# WindVane_1.net
KiCad netlist of a schematic drawn in EAGLE
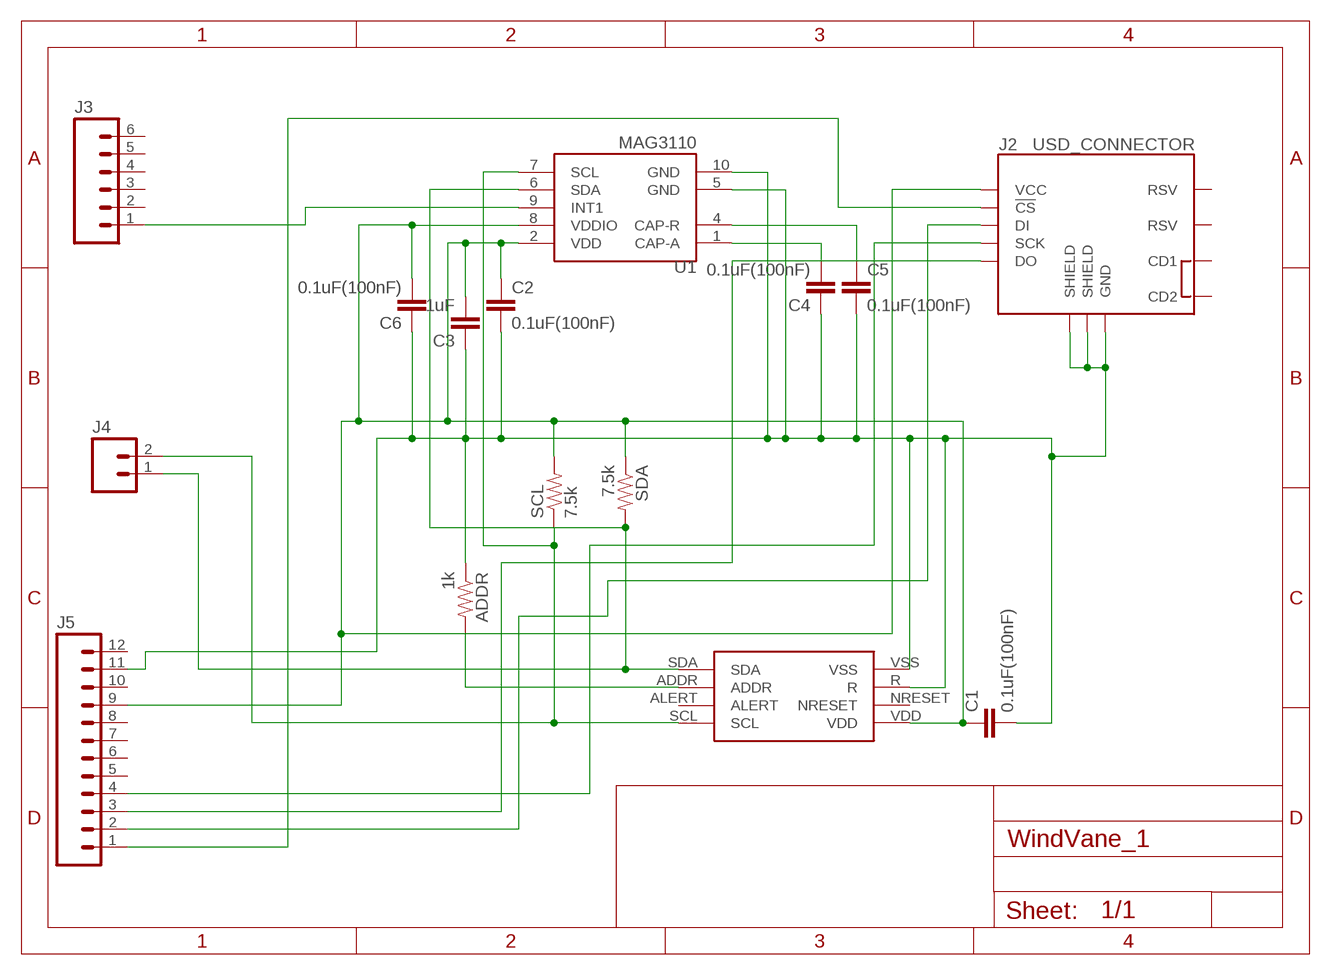
[diagram p0: schematic, sheet 1]

(export (version "E")
  (design (tool "Eeschema 10.0.6"))
  (components
    (comp (ref "ADDR")
      (value "1k")
      (footprint "eagle-import:1206")
      (libsource (lib "eagle-import") (part "RESISTOR1206"))
    )
    (comp (ref "C1")
      (value "0.1uF(100nF)")
      (footprint "eagle-import:0603-CAP")
      (libsource (lib "eagle-import") (part "SparkFun-Passives_CAP0603-CAP"))
    )
    (comp (ref "C2")
      (value "0.1uF(100nF)")
      (footprint "eagle-import:0603-CAP")
      (libsource (lib "eagle-import") (part "0.1UF-25V(+80/-20%)(0603)"))
    )
    (comp (ref "C3")
      (value "1uF")
      (footprint "eagle-import:0402-CAP")
      (libsource (lib "eagle-import") (part "CAP0402-CAP"))
    )
    (comp (ref "C4")
      (value "0.1uF(100nF)")
      (footprint "eagle-import:0603-CAP")
      (libsource (lib "eagle-import") (part "0.1UF-25V(+80/-20%)(0603)"))
    )
    (comp (ref "C5")
      (value "0.1uF(100nF)")
      (footprint "eagle-import:0603-CAP")
      (libsource (lib "eagle-import") (part "0.1UF-25V(+80/-20%)(0603)"))
    )
    (comp (ref "C6")
      (value "0.1uF(100nF)")
      (footprint "eagle-import:0603-CAP")
      (libsource (lib "eagle-import") (part "0.1UF-25V(+80/-20%)(0603)"))
    )
    (comp (ref "J2")
      (value "USD_CONNECTOR")
      (footprint "eagle-import:MICRO-SD-SOCKET-PP")
      (libsource (lib "eagle-import") (part "USD_CONNECTOR"))
    )
    (comp (ref "J3")
      (value "M06NO_SILK_YES_STOP")
      (footprint "eagle-import:1X06_NO_SILK_YES_STOP")
      (libsource (lib "eagle-import") (part "M06NO_SILK_YES_STOP"))
    )
    (comp (ref "J4")
      (value "M02PTH")
      (footprint "eagle-import:1X02")
      (libsource (lib "eagle-import") (part "M02PTH"))
    )
    (comp (ref "J5")
      (value "M121X12_NO_SILK_KIT")
      (footprint "eagle-import:1X12_NO_SILK_KIT")
      (libsource (lib "eagle-import") (part "M121X12_NO_SILK_KIT"))
    )
    (comp (ref "SCL")
      (value "7.5k")
      (footprint "eagle-import:1206")
      (libsource (lib "eagle-import") (part "RESISTOR1206"))
    )
    (comp (ref "SDA")
      (value "7.5k")
      (footprint "eagle-import:1206")
      (libsource (lib "eagle-import") (part "RESISTOR1206"))
    )
    (comp (ref "U$1")
      (value "SHT3X-DISSURFACE_MOUNT")
      (footprint "eagle-import:SHT3X-DIS")
      (libsource (lib "eagle-import") (part "SHT3X-DISSURFACE_MOUNT"))
    )
    (comp (ref "U1")
      (value "MAG3110")
      (footprint "eagle-import:DFN-10")
      (libsource (lib "eagle-import") (part "MAG3110"))
    )
  )
  (nets
    (net (code "1") (name "Net-(ADDR-Pad1)") (class "Default")
      (node (ref "ADDR") (pin "1") (pinfunction "1_1") (pintype "passive"))
      (node (ref "C1") (pin "2") (pinfunction "2_2") (pintype "passive"))
      (node (ref "C2") (pin "2") (pinfunction "2_2") (pintype "passive"))
      (node (ref "C3") (pin "1") (pinfunction "1_1") (pintype "passive"))
      (node (ref "C4") (pin "1") (pinfunction "1_1") (pintype "passive"))
      (node (ref "C5") (pin "2") (pinfunction "2_2") (pintype "passive"))
      (node (ref "C6") (pin "1") (pinfunction "1_1") (pintype "passive"))
      (node (ref "J2") (pin "GND") (pinfunction "GND_GND") (pintype "bidirectional"))
      (node (ref "J2") (pin "GND1") (pinfunction "SHIELD_GND1") (pintype "bidirectional"))
      (node (ref "J2") (pin "GND3") (pinfunction "SHIELD_GND3") (pintype "bidirectional"))
      (node (ref "J5") (pin "11") (pinfunction "11_11") (pintype "passive"))
      (node (ref "U$1") (pin "R") (pinfunction "R_R") (pintype "bidirectional"))
      (node (ref "U$1") (pin "VSS") (pinfunction "VSS_VSS") (pintype "bidirectional"))
      (node (ref "U1") (pin "10") (pinfunction "GND_10") (pintype "bidirectional"))
      (node (ref "U1") (pin "5") (pinfunction "GND_5") (pintype "bidirectional"))
    )
    (net (code "2") (name "Net-(ADDR-Pad2)") (class "Default")
      (node (ref "ADDR") (pin "2") (pinfunction "2_2") (pintype "passive"))
      (node (ref "U$1") (pin "ADDR") (pinfunction "ADDR_ADDR") (pintype "bidirectional"))
    )
    (net (code "3") (name "Net-(J2-PadDI)") (class "Default")
      (node (ref "J2") (pin "DI") (pinfunction "DI_DI") (pintype "bidirectional"))
      (node (ref "J5") (pin "2") (pinfunction "2_2") (pintype "passive"))
    )
    (net (code "4") (name "Net-(J2-PadDO)") (class "Default")
      (node (ref "J2") (pin "DO") (pinfunction "DO_DO") (pintype "bidirectional"))
      (node (ref "J5") (pin "3") (pinfunction "3_3") (pintype "passive"))
    )
    (net (code "5") (name "Net-(J2-SCK)") (class "Default")
      (node (ref "J2") (pin "SCLK") (pinfunction "SCK_SCLK") (pintype "bidirectional"))
      (node (ref "J5") (pin "4") (pinfunction "4_4") (pintype "passive"))
    )
    (net (code "6") (name "Net-(J2-~{CS})") (class "Default")
      (node (ref "J2") (pin "CS") (pinfunction "~{CS}_CS") (pintype "bidirectional"))
      (node (ref "J5") (pin "1") (pinfunction "1_1") (pintype "passive"))
    )
    (net (code "7") (name "Net-(U1-CAP-A)") (class "Default")
      (node (ref "C4") (pin "2") (pinfunction "2_2") (pintype "passive"))
      (node (ref "U1") (pin "1") (pinfunction "CAP-A_1") (pintype "bidirectional"))
    )
    (net (code "8") (name "Net-(U1-CAP-R)") (class "Default")
      (node (ref "C5") (pin "1") (pinfunction "1_1") (pintype "passive"))
      (node (ref "U1") (pin "4") (pinfunction "CAP-R_4") (pintype "bidirectional"))
    )
    (net (code "9") (name "Net-(U1-INT1)") (class "Default")
      (node (ref "J3") (pin "1") (pinfunction "1_1") (pintype "passive"))
      (node (ref "U1") (pin "9") (pinfunction "INT1_9") (pintype "bidirectional"))
    )
    (net (code "10") (name "Net-(U1-SCL)") (class "Default")
      (node (ref "J4") (pin "2") (pinfunction "2_2") (pintype "passive"))
      (node (ref "SCL") (pin "1") (pinfunction "1_1") (pintype "passive"))
      (node (ref "U$1") (pin "SCL") (pinfunction "SCL_SCL") (pintype "bidirectional"))
      (node (ref "U1") (pin "7") (pinfunction "SCL_7") (pintype "bidirectional"))
    )
    (net (code "11") (name "Net-(U1-SDA)") (class "Default")
      (node (ref "J4") (pin "1") (pinfunction "1_1") (pintype "passive"))
      (node (ref "SDA") (pin "2") (pinfunction "2_2") (pintype "passive"))
      (node (ref "U$1") (pin "SDA") (pinfunction "SDA_SDA") (pintype "bidirectional"))
      (node (ref "U1") (pin "6") (pinfunction "SDA_6") (pintype "bidirectional"))
    )
    (net (code "12") (name "Net-(U1-VDD)") (class "Default")
      (node (ref "C1") (pin "1") (pinfunction "1_1") (pintype "passive"))
      (node (ref "C2") (pin "1") (pinfunction "1_1") (pintype "passive"))
      (node (ref "C3") (pin "2") (pinfunction "2_2") (pintype "passive"))
      (node (ref "C6") (pin "2") (pinfunction "2_2") (pintype "passive"))
      (node (ref "J2") (pin "VCC") (pinfunction "VCC_VCC") (pintype "bidirectional"))
      (node (ref "J5") (pin "9") (pinfunction "9_9") (pintype "passive"))
      (node (ref "SCL") (pin "2") (pinfunction "2_2") (pintype "passive"))
      (node (ref "SDA") (pin "1") (pinfunction "1_1") (pintype "passive"))
      (node (ref "U$1") (pin "VDD") (pinfunction "VDD_VDD") (pintype "bidirectional"))
      (node (ref "U1") (pin "2") (pinfunction "VDD_2") (pintype "bidirectional"))
      (node (ref "U1") (pin "8") (pinfunction "VDDIO_8") (pintype "bidirectional"))
    )
    (net (code "13") (name "unconnected-(J2-PadCD1)") (class "Default")
      (node (ref "J2") (pin "CD1") (pinfunction "CD1_CD1") (pintype "bidirectional"))
    )
    (net (code "14") (name "unconnected-(J2-PadCD2)") (class "Default")
      (node (ref "J2") (pin "CD2") (pinfunction "CD2_CD2") (pintype "bidirectional"))
    )
    (net (code "15") (name "unconnected-(J2-RSV-PadRSV1)") (class "Default")
      (node (ref "J2") (pin "RSV1") (pinfunction "RSV_RSV1") (pintype "bidirectional"))
    )
    (net (code "16") (name "unconnected-(J2-RSV-PadRSV2)") (class "Default")
      (node (ref "J2") (pin "RSV2") (pinfunction "RSV_RSV2") (pintype "bidirectional"))
    )
    (net (code "17") (name "unconnected-(J3-Pad2)") (class "Default")
      (node (ref "J3") (pin "2") (pinfunction "2_2") (pintype "passive"))
    )
    (net (code "18") (name "unconnected-(J3-Pad3)") (class "Default")
      (node (ref "J3") (pin "3") (pinfunction "3_3") (pintype "passive"))
    )
    (net (code "19") (name "unconnected-(J3-Pad4)") (class "Default")
      (node (ref "J3") (pin "4") (pinfunction "4_4") (pintype "passive"))
    )
    (net (code "20") (name "unconnected-(J3-Pad5)") (class "Default")
      (node (ref "J3") (pin "5") (pinfunction "5_5") (pintype "passive"))
    )
    (net (code "21") (name "unconnected-(J3-Pad6)") (class "Default")
      (node (ref "J3") (pin "6") (pinfunction "6_6") (pintype "passive"))
    )
    (net (code "22") (name "unconnected-(J5-Pad5)") (class "Default")
      (node (ref "J5") (pin "5") (pinfunction "5_5") (pintype "passive"))
    )
    (net (code "23") (name "unconnected-(J5-Pad6)") (class "Default")
      (node (ref "J5") (pin "6") (pinfunction "6_6") (pintype "passive"))
    )
    (net (code "24") (name "unconnected-(J5-Pad7)") (class "Default")
      (node (ref "J5") (pin "7") (pinfunction "7_7") (pintype "passive"))
    )
    (net (code "25") (name "unconnected-(J5-Pad8)") (class "Default")
      (node (ref "J5") (pin "8") (pinfunction "8_8") (pintype "passive"))
    )
    (net (code "26") (name "unconnected-(J5-Pad10)") (class "Default")
      (node (ref "J5") (pin "10") (pinfunction "10_10") (pintype "passive"))
    )
    (net (code "27") (name "unconnected-(J5-Pad12)") (class "Default")
      (node (ref "J5") (pin "12") (pinfunction "12_12") (pintype "passive"))
    )
    (net (code "28") (name "unconnected-(U$1-PadALERT)") (class "Default")
      (node (ref "U$1") (pin "ALERT") (pinfunction "ALERT_ALERT") (pintype "bidirectional"))
    )
    (net (code "29") (name "unconnected-(U$1-PadNRESET)") (class "Default")
      (node (ref "U$1") (pin "NRESET") (pinfunction "NRESET_NRESET") (pintype "bidirectional"))
    )
  )
)
